# ERN_MainPowerV2_2.net
KiCad netlist of a schematic drawn in Altium Designer
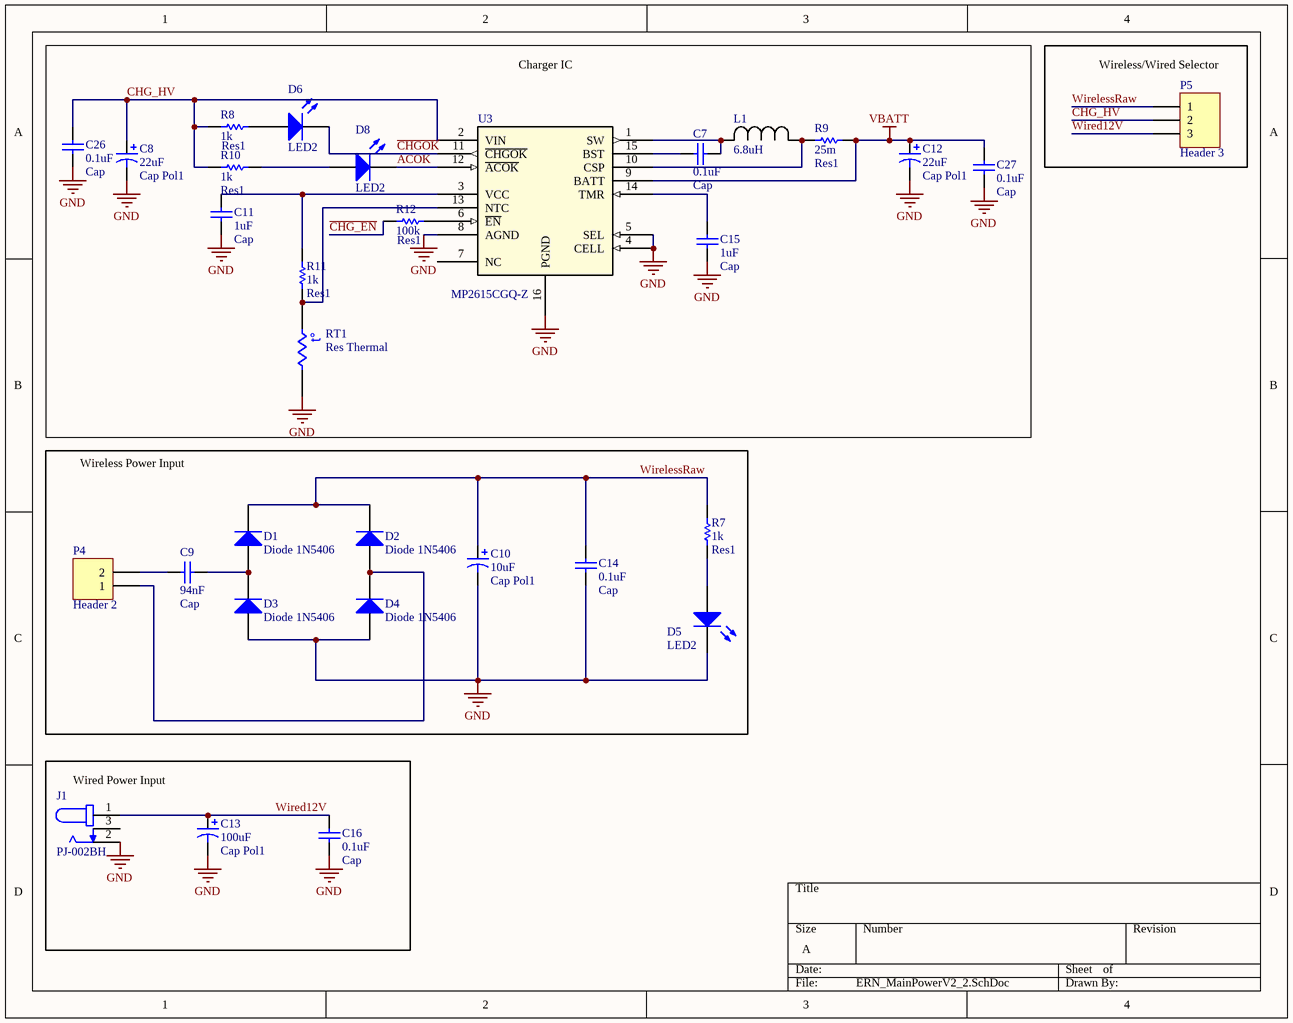
[diagram p0: ERN_MainPowerV2_2.SchDoc]

(export (version "E")
  (design (tool "Eeschema 10.0.6"))
  (components
    (comp (ref "C7")
      (value "Cap")
      (footprint "C0805")
      (description "Capacitor")
      (fields (field (name "ALTIUM_VALUE") "0.1uF") (field (name "PUBLISHER") "Altium Limited"))
      (libsource (lib "Miscellaneous Devices") (part "Cap"))
    )
    (comp (ref "C8")
      (value "Cap Pol1")
      (footprint "Cap_47uF_100uF")
      (description "Polarized Capacitor (Radial)")
      (fields (field (name "ALTIUM_VALUE") "22uF") (field (name "PUBLISHER") "Altium Limited"))
      (libsource (lib "Miscellaneous Devices") (part "Cap Pol1"))
    )
    (comp (ref "C9")
      (value "Cap")
      (footprint "C1210")
      (description "Capacitor")
      (fields (field (name "ALTIUM_VALUE") "94nF") (field (name "PUBLISHER") "Altium Limited"))
      (libsource (lib "Miscellaneous Devices") (part "Cap"))
    )
    (comp (ref "C10")
      (value "Cap Pol1")
      (footprint "Cap_47uF_100uF")
      (description "Polarized Capacitor (Radial)")
      (fields (field (name "ALTIUM_VALUE") "10uF") (field (name "PUBLISHER") "Altium Limited"))
      (libsource (lib "Miscellaneous Devices") (part "Cap Pol1"))
    )
    (comp (ref "C11")
      (value "Cap")
      (footprint "C0805")
      (description "Capacitor")
      (fields (field (name "ALTIUM_VALUE") "1uF") (field (name "PUBLISHER") "Altium Limited"))
      (libsource (lib "Miscellaneous Devices") (part "Cap"))
    )
    (comp (ref "C12")
      (value "Cap Pol1")
      (footprint "Cap_47uF_100uF")
      (description "Polarized Capacitor (Radial)")
      (fields (field (name "ALTIUM_VALUE") "22uF") (field (name "PUBLISHER") "Altium Limited"))
      (libsource (lib "Miscellaneous Devices") (part "Cap Pol1"))
    )
    (comp (ref "C13")
      (value "Cap Pol1")
      (footprint "Cap_47uF_100uF")
      (description "Polarized Capacitor (Radial)")
      (fields (field (name "ALTIUM_VALUE") "100uF") (field (name "PUBLISHER") "Altium Limited"))
      (libsource (lib "Miscellaneous Devices") (part "Cap Pol1"))
    )
    (comp (ref "C14")
      (value "Cap")
      (footprint "RAD-0.3")
      (description "Capacitor")
      (fields (field (name "ALTIUM_VALUE") "0.1uF") (field (name "PUBLISHER") "Altium Limited"))
      (libsource (lib "Miscellaneous Devices") (part "Cap"))
    )
    (comp (ref "C15")
      (value "Cap")
      (footprint "C0805")
      (description "Capacitor")
      (fields (field (name "ALTIUM_VALUE") "1uF") (field (name "PUBLISHER") "Altium Limited"))
      (libsource (lib "Miscellaneous Devices") (part "Cap"))
    )
    (comp (ref "C16")
      (value "Cap")
      (footprint "RAD-0.3")
      (description "Capacitor")
      (fields (field (name "ALTIUM_VALUE") "0.1uF") (field (name "PUBLISHER") "Altium Limited"))
      (libsource (lib "Miscellaneous Devices") (part "Cap"))
    )
    (comp (ref "C26")
      (value "Cap")
      (footprint "C0805")
      (description "Capacitor")
      (fields (field (name "ALTIUM_VALUE") "0.1uF") (field (name "PUBLISHER") "Altium Limited"))
      (libsource (lib "Miscellaneous Devices") (part "Cap"))
    )
    (comp (ref "C27")
      (value "Cap")
      (footprint "rad-0.3")
      (description "Capacitor")
      (fields (field (name "ALTIUM_VALUE") "0.1uF") (field (name "PUBLISHER") "Altium Limited"))
      (libsource (lib "Miscellaneous Devices") (part "Cap"))
    )
    (comp (ref "D1")
      (value "Diode 1N5406")
      (footprint "DO-201AD")
      (description "3 Amp General Purpose Rectifier")
      (fields (field (name "PUBLISHER") "Altium Limited"))
      (libsource (lib "Miscellaneous Devices") (part "Diode 1N5406"))
    )
    (comp (ref "D2")
      (value "Diode 1N5406")
      (footprint "DO-201AD")
      (description "3 Amp General Purpose Rectifier")
      (fields (field (name "PUBLISHER") "Altium Limited"))
      (libsource (lib "Miscellaneous Devices") (part "Diode 1N5406"))
    )
    (comp (ref "D3")
      (value "Diode 1N5406")
      (footprint "DO-201AD")
      (description "3 Amp General Purpose Rectifier")
      (fields (field (name "PUBLISHER") "Altium Limited"))
      (libsource (lib "Miscellaneous Devices") (part "Diode 1N5406"))
    )
    (comp (ref "D4")
      (value "Diode 1N5406")
      (footprint "DO-201AD")
      (description "3 Amp General Purpose Rectifier")
      (fields (field (name "PUBLISHER") "Altium Limited"))
      (libsource (lib "Miscellaneous Devices") (part "Diode 1N5406"))
    )
    (comp (ref "D5")
      (value "LED2")
      (footprint "led-0")
      (description "Typical RED, GREEN, YELLOW, AMBER GaAs LED")
      (fields (field (name "PUBLISHER") "Altium Limited"))
      (libsource (lib "Miscellaneous Devices") (part "LED2"))
    )
    (comp (ref "D6")
      (value "LED2")
      (footprint "led-0")
      (description "Typical RED, GREEN, YELLOW, AMBER GaAs LED")
      (fields (field (name "PUBLISHER") "Altium Limited"))
      (libsource (lib "Miscellaneous Devices") (part "LED2"))
    )
    (comp (ref "D8")
      (value "LED2")
      (footprint "led-0")
      (description "Typical RED, GREEN, YELLOW, AMBER GaAs LED")
      (fields (field (name "PUBLISHER") "Altium Limited"))
      (libsource (lib "Miscellaneous Devices") (part "LED2"))
    )
    (comp (ref "J1")
      (value "PJ-002BH")
      (footprint "CUI_PJ-002BH")
      (description "2.5 x 6.5 mm, 5.0 A, Horizontal, Through Hole, Dc Power Jack Connector")
      (fields (field (name "MF") "Same Sky"))
      (libsource (lib "ERN") (part "PJ-002BH"))
    )
    (comp (ref "L1")
      (value "6.8uH")
      (footprint "IND_VLS6045EX-6R8M")
      (description "Inductor 68uH")
      (fields
        (field (name "MANUFACTURER_PART_NUMBER") "2111-V-RC")
        (field (name "COPYRIGHT") "Copyright (C) 2026 Ultra Librarian. All rights reserved.")
      )
      (libsource (lib "ERN") (part "2111-V-RC"))
    )
    (comp (ref "P4")
      (value "Header 2")
      (footprint "HDR1X2")
      (description "Header, 2-Pin")
      (fields (field (name "PUBLISHER") "Altium Limited"))
      (libsource (lib "Miscellaneous Connectors") (part "Header 2"))
    )
    (comp (ref "P5")
      (value "Header 3")
      (footprint "HDR1X3")
      (description "Header, 3-Pin")
      (fields (field (name "PUBLISHER") "Altium Limited"))
      (libsource (lib "Miscellaneous Connectors") (part "Header 3"))
    )
    (comp (ref "R7")
      (value "Res1")
      (footprint "AXIAL-0.3")
      (description "Resistor")
      (fields (field (name "ALTIUM_VALUE") "1k") (field (name "PUBLISHER") "Altium Limited"))
      (libsource (lib "Miscellaneous Devices") (part "Res1"))
    )
    (comp (ref "R8")
      (value "Res1")
      (footprint "AXIAL-0.3")
      (description "Resistor")
      (fields (field (name "ALTIUM_VALUE") "1k") (field (name "PUBLISHER") "Altium Limited"))
      (libsource (lib "Miscellaneous Devices") (part "Res1"))
    )
    (comp (ref "R9")
      (value "Res1")
      (footprint "RESC6432X90N")
      (description "Resistor")
      (fields (field (name "ALTIUM_VALUE") "25m") (field (name "PUBLISHER") "Altium Limited"))
      (libsource (lib "Miscellaneous Devices") (part "Res1"))
    )
    (comp (ref "R10")
      (value "Res1")
      (footprint "AXIAL-0.3")
      (description "Resistor")
      (fields (field (name "ALTIUM_VALUE") "1k") (field (name "PUBLISHER") "Altium Limited"))
      (libsource (lib "Miscellaneous Devices") (part "Res1"))
    )
    (comp (ref "R11")
      (value "Res1")
      (footprint "AXIAL-0.3")
      (description "Resistor")
      (fields (field (name "ALTIUM_VALUE") "1k") (field (name "PUBLISHER") "Altium Limited"))
      (libsource (lib "Miscellaneous Devices") (part "Res1"))
    )
    (comp (ref "R12")
      (value "Res1")
      (footprint "AXIAL-0.3")
      (description "Resistor")
      (fields (field (name "ALTIUM_VALUE") "100k") (field (name "PUBLISHER") "Altium Limited"))
      (libsource (lib "Miscellaneous Devices") (part "Res1"))
    )
    (comp (ref "RT1")
      (value "Res Thermal")
      (footprint "AXIAL-0.3")
      (description "Thermistor")
      (fields (field (name "PUBLISHER") "Altium Limited"))
      (libsource (lib "Miscellaneous Devices") (part "Res Thermal"))
    )
    (comp (ref "U3")
      (value "MP2615CGQ-Z")
      (footprint "QFN-16_3MM×3MM_MNP_MPS")
      (description "2.1A 1- or 2-Cell Li-ion Battery Charger with 25mohm Rsns")
      (fields (field (name "COPYRIGHT") "Copyright (C) 2026 Ultra Librarian. All rights reserved."))
      (libsource (lib "ERN") (part "MP2615CGQ-Z"))
    )
  )
  (nets
    (net (code "1") (name "/CHG_HV") (class "Default")
      (node (ref "C26") (pin "2") (pinfunction "2_2") (pintype "passive"))
      (node (ref "C8") (pin "1") (pinfunction "1_1") (pintype "passive"))
      (node (ref "P5") (pin "2") (pinfunction "2_2") (pintype "passive"))
      (node (ref "R10") (pin "2") (pinfunction "2_2") (pintype "passive"))
      (node (ref "R8") (pin "2") (pinfunction "2_2") (pintype "passive"))
      (node (ref "U3") (pin "2") (pinfunction "VIN_2") (pintype "power_in"))
    )
    (net (code "2") (name "/Wired12V") (class "Default")
      (node (ref "C13") (pin "1") (pinfunction "1_1") (pintype "passive"))
      (node (ref "C16") (pin "1") (pinfunction "1_1") (pintype "passive"))
      (node (ref "J1") (pin "1") (pinfunction "1_1") (pintype "passive"))
      (node (ref "P5") (pin "3") (pinfunction "3_3") (pintype "passive"))
    )
    (net (code "3") (name "/WirelessRaw") (class "Default")
      (node (ref "C10") (pin "1") (pinfunction "1_1") (pintype "passive"))
      (node (ref "C14") (pin "1") (pinfunction "1_1") (pintype "passive"))
      (node (ref "D1") (pin "2") (pinfunction "K_2") (pintype "passive"))
      (node (ref "D2") (pin "2") (pinfunction "K_2") (pintype "passive"))
      (node (ref "P5") (pin "1") (pinfunction "1_1") (pintype "passive"))
      (node (ref "R7") (pin "2") (pinfunction "2_2") (pintype "passive"))
    )
    (net (code "4") (name "/~{ACOK}") (class "Default")
      (node (ref "D8") (pin "2") (pinfunction "K_2") (pintype "passive"))
      (node (ref "U3") (pin "12") (pinfunction "~{ACOK}_12") (pintype "input"))
    )
    (net (code "5") (name "/~{CHGOK}") (class "Default")
      (node (ref "D6") (pin "2") (pinfunction "K_2") (pintype "passive"))
      (node (ref "U3") (pin "11") (pinfunction "~{CHGOK}_11") (pintype "output"))
    )
    (net (code "6") (name "/~{CHG_EN}") (class "Default")
      (node (ref "R12") (pin "2") (pinfunction "2_2") (pintype "passive"))
    )
    (net (code "7") (name "GND") (class "Default")
      (node (ref "C10") (pin "2") (pinfunction "2_2") (pintype "passive"))
      (node (ref "C11") (pin "1") (pinfunction "1_1") (pintype "passive"))
      (node (ref "C12") (pin "2") (pinfunction "2_2") (pintype "passive"))
      (node (ref "C13") (pin "2") (pinfunction "2_2") (pintype "passive"))
      (node (ref "C14") (pin "2") (pinfunction "2_2") (pintype "passive"))
      (node (ref "C15") (pin "2") (pinfunction "2_2") (pintype "passive"))
      (node (ref "C16") (pin "2") (pinfunction "2_2") (pintype "passive"))
      (node (ref "C26") (pin "1") (pinfunction "1_1") (pintype "passive"))
      (node (ref "C27") (pin "2") (pinfunction "2_2") (pintype "passive"))
      (node (ref "C8") (pin "2") (pinfunction "2_2") (pintype "passive"))
      (node (ref "D3") (pin "1") (pinfunction "A_1") (pintype "passive"))
      (node (ref "D4") (pin "1") (pinfunction "A_1") (pintype "passive"))
      (node (ref "D5") (pin "2") (pinfunction "K_2") (pintype "passive"))
      (node (ref "J1") (pin "2") (pinfunction "2_2") (pintype "passive"))
      (node (ref "RT1") (pin "2") (pinfunction "2_2") (pintype "passive"))
      (node (ref "U3") (pin "16") (pinfunction "PGND_16") (pintype "power_in"))
      (node (ref "U3") (pin "4") (pinfunction "CELL_4") (pintype "input"))
      (node (ref "U3") (pin "5") (pinfunction "SEL_5") (pintype "input"))
      (node (ref "U3") (pin "8") (pinfunction "AGND_8") (pintype "power_in"))
    )
    (net (code "8") (name "Net-(C9-Pad1)") (class "Default")
      (node (ref "C9") (pin "1") (pinfunction "1_1") (pintype "passive"))
      (node (ref "P4") (pin "2") (pinfunction "2_2") (pintype "passive"))
    )
    (net (code "9") (name "Net-(D1-A)") (class "Default")
      (node (ref "C9") (pin "2") (pinfunction "2_2") (pintype "passive"))
      (node (ref "D1") (pin "1") (pinfunction "A_1") (pintype "passive"))
      (node (ref "D3") (pin "2") (pinfunction "K_2") (pintype "passive"))
    )
    (net (code "10") (name "Net-(D2-A)") (class "Default")
      (node (ref "D2") (pin "1") (pinfunction "A_1") (pintype "passive"))
      (node (ref "D4") (pin "2") (pinfunction "K_2") (pintype "passive"))
      (node (ref "P4") (pin "1") (pinfunction "1_1") (pintype "passive"))
    )
    (net (code "11") (name "Net-(D5-A)") (class "Default")
      (node (ref "D5") (pin "1") (pinfunction "A_1") (pintype "passive"))
      (node (ref "R7") (pin "1") (pinfunction "1_1") (pintype "passive"))
    )
    (net (code "12") (name "Net-(D6-A)") (class "Default")
      (node (ref "D6") (pin "1") (pinfunction "A_1") (pintype "passive"))
      (node (ref "R8") (pin "1") (pinfunction "1_1") (pintype "passive"))
    )
    (net (code "13") (name "Net-(D8-A)") (class "Default")
      (node (ref "D8") (pin "1") (pinfunction "A_1") (pintype "passive"))
      (node (ref "R10") (pin "1") (pinfunction "1_1") (pintype "passive"))
    )
    (net (code "14") (name "Net-(U3-BST)") (class "Default")
      (node (ref "C7") (pin "1") (pinfunction "1_1") (pintype "passive"))
      (node (ref "U3") (pin "15") (pinfunction "BST_15") (pintype "power_in"))
    )
    (net (code "15") (name "Net-(U3-CSP)") (class "Default")
      (node (ref "L1") (pin "1") (pinfunction "1_1") (pintype "passive"))
      (node (ref "R9") (pin "1") (pinfunction "1_1") (pintype "passive"))
      (node (ref "U3") (pin "10") (pinfunction "CSP_10") (pintype "power_in"))
    )
    (net (code "16") (name "Net-(U3-NTC)") (class "Default")
      (node (ref "R11") (pin "2") (pinfunction "2_2") (pintype "passive"))
      (node (ref "RT1") (pin "1") (pinfunction "1_1") (pintype "passive"))
      (node (ref "U3") (pin "13") (pinfunction "NTC_13") (pintype "power_in"))
    )
    (net (code "17") (name "Net-(U3-SW)") (class "Default")
      (node (ref "C7") (pin "2") (pinfunction "2_2") (pintype "passive"))
      (node (ref "L1") (pin "2") (pinfunction "2_2") (pintype "passive"))
      (node (ref "U3") (pin "1") (pinfunction "SW_1") (pintype "output"))
    )
    (net (code "18") (name "Net-(U3-TMR)") (class "Default")
      (node (ref "C15") (pin "1") (pinfunction "1_1") (pintype "passive"))
      (node (ref "U3") (pin "14") (pinfunction "TMR_14") (pintype "input"))
    )
    (net (code "19") (name "Net-(U3-VCC)") (class "Default")
      (node (ref "C11") (pin "2") (pinfunction "2_2") (pintype "passive"))
      (node (ref "R11") (pin "1") (pinfunction "1_1") (pintype "passive"))
      (node (ref "U3") (pin "3") (pinfunction "VCC_3") (pintype "power_in"))
    )
    (net (code "20") (name "Net-(U3-~{EN})") (class "Default")
      (node (ref "R12") (pin "1") (pinfunction "1_1") (pintype "passive"))
      (node (ref "U3") (pin "6") (pinfunction "~{EN}_6") (pintype "input"))
    )
    (net (code "21") (name "VBATT") (class "Default")
      (node (ref "C12") (pin "1") (pinfunction "1_1") (pintype "passive"))
      (node (ref "C27") (pin "1") (pinfunction "1_1") (pintype "passive"))
      (node (ref "R9") (pin "2") (pinfunction "2_2") (pintype "passive"))
      (node (ref "U3") (pin "9") (pinfunction "BATT_9") (pintype "power_in"))
    )
    (net (code "22") (name "unconnected-(J1-Pad3)") (class "Default")
      (node (ref "J1") (pin "3") (pinfunction "3_3") (pintype "passive"))
    )
    (net (code "23") (name "unconnected-(U3-NC-Pad7)") (class "Default")
      (node (ref "U3") (pin "7") (pinfunction "NC_7") (pintype "passive"))
    )
  )
)
